# etna-main-driver.net
KiCad netlist of a schematic drawn in Altium Designer
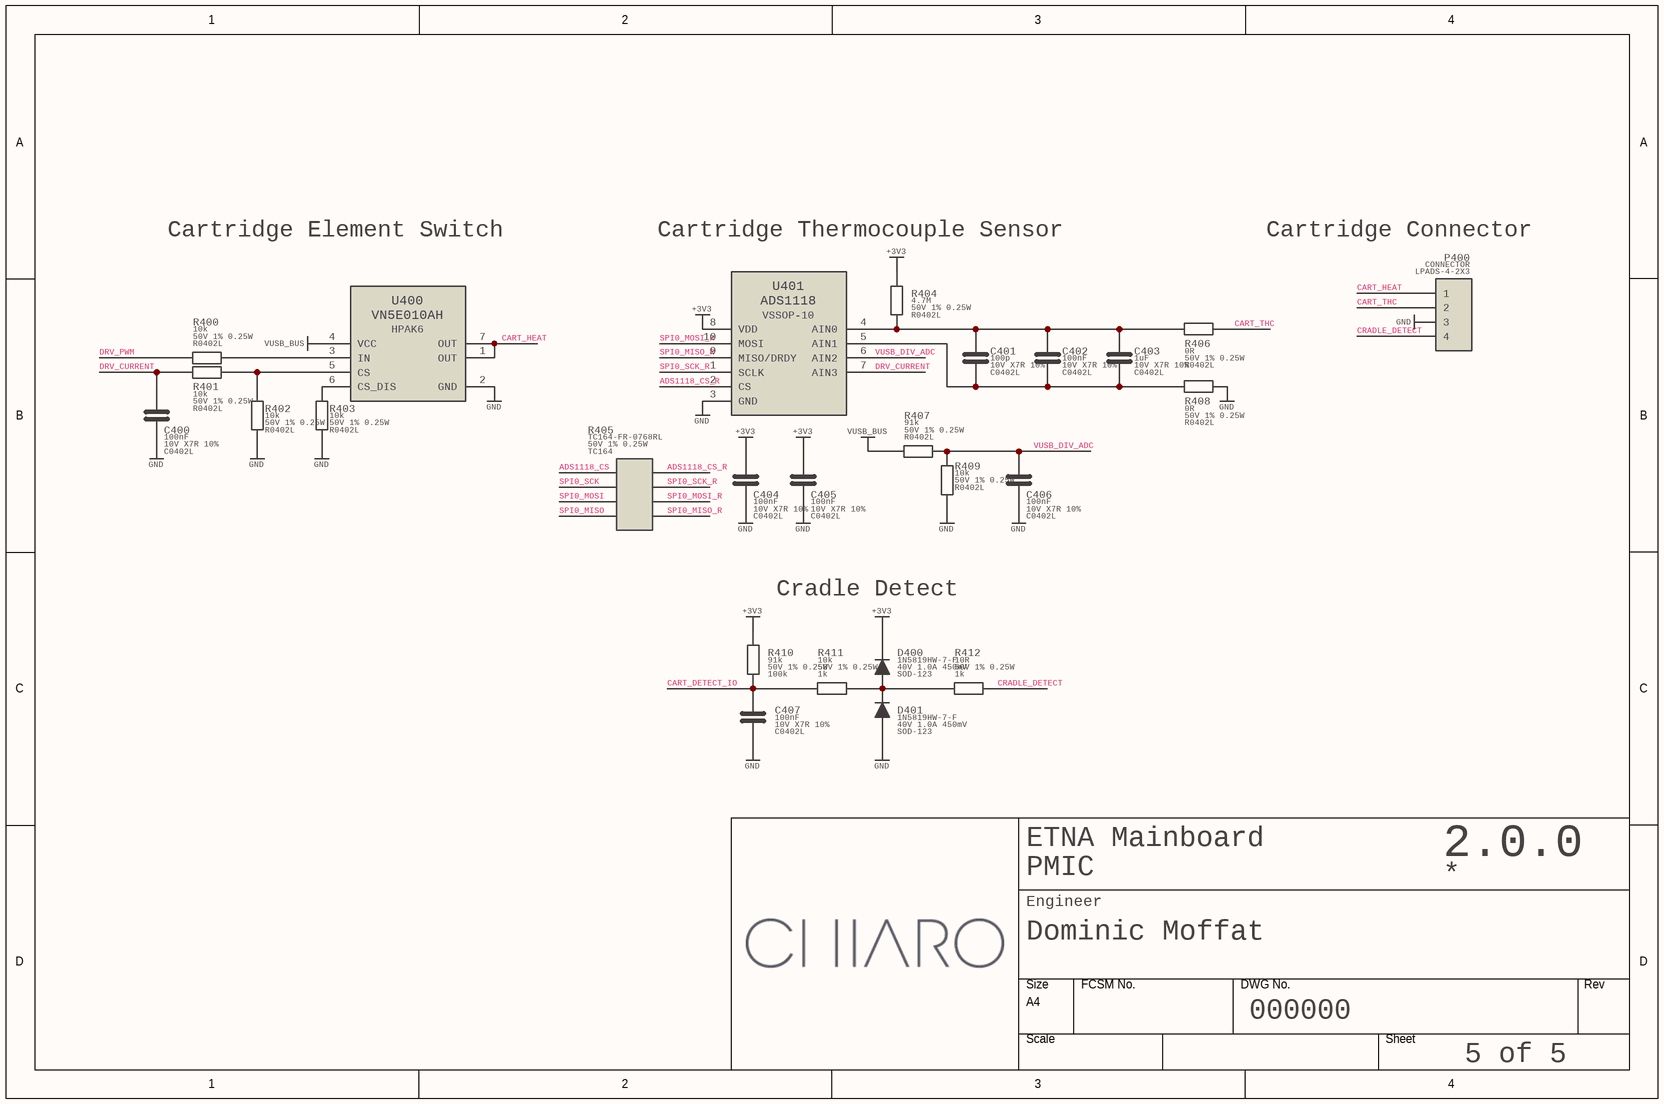
[diagram p0: etna-main-driver.SchDoc]

(export (version "E")
  (design (tool "Eeschema 10.0.6"))
  (components
    (comp (ref "C400")
      (value "100nF")
      (footprint "C0402L")
      (fields (field (name "SPECIFICATION") "10V X7R 10%"))
      (libsource (lib "passive") (part "CAPACITOR_NONPOL"))
    )
    (comp (ref "C401")
      (value "100p")
      (footprint "C0402L")
      (fields (field (name "SPECIFICATION") "10V X7R 10%"))
      (libsource (lib "passive") (part "CAPACITOR_NONPOL"))
    )
    (comp (ref "C402")
      (value "100nF")
      (footprint "C0402L")
      (fields (field (name "SPECIFICATION") "10V X7R 10%"))
      (libsource (lib "passive") (part "CAPACITOR_NONPOL"))
    )
    (comp (ref "C403")
      (value "1uF")
      (footprint "C0402L")
      (fields (field (name "SPECIFICATION") "10V X7R 10%"))
      (libsource (lib "passive") (part "CAPACITOR_NONPOL"))
    )
    (comp (ref "C404")
      (value "100nF")
      (footprint "C0402L")
      (fields (field (name "SPECIFICATION") "10V X7R 10%"))
      (libsource (lib "passive") (part "CAPACITOR_NONPOL"))
    )
    (comp (ref "C405")
      (value "100nF")
      (footprint "C0402L")
      (fields (field (name "SPECIFICATION") "10V X7R 10%"))
      (libsource (lib "passive") (part "CAPACITOR_NONPOL"))
    )
    (comp (ref "C406")
      (value "100nF")
      (footprint "C0402L")
      (fields (field (name "SPECIFICATION") "10V X7R 10%"))
      (libsource (lib "passive") (part "CAPACITOR_NONPOL"))
    )
    (comp (ref "C407")
      (value "100nF")
      (footprint "C0402L")
      (fields (field (name "SPECIFICATION") "10V X7R 10%"))
      (libsource (lib "passive") (part "CAPACITOR_NONPOL"))
    )
    (comp (ref "D400")
      (value "1N5819HW-7-F")
      (footprint "SOD-123")
      (fields (field (name "SPECIFICATION") "40V 1.0A 450mV") (field (name "Comment") "DIODE"))
      (libsource (lib "discreet") (part "DIODE"))
    )
    (comp (ref "D401")
      (value "1N5819HW-7-F")
      (footprint "SOD-123")
      (fields (field (name "SPECIFICATION") "40V 1.0A 450mV") (field (name "Comment") "DIODE"))
      (libsource (lib "discreet") (part "DIODE"))
    )
    (comp (ref "P400")
      (value "CONNECTOR")
      (footprint "LPADS-4-2X3")
      (fields (field (name "Comment") "H4"))
      (libsource (lib "connectors") (part "H4"))
    )
    (comp (ref "R400")
      (value "10k")
      (footprint "R0402L")
      (fields (field (name "SPECIFICATION") "50V 1% 0.25W") (field (name "Comment") "RESISTOR"))
      (libsource (lib "") (part "RESISTOR_1"))
    )
    (comp (ref "R401")
      (value "10k")
      (footprint "R0402L")
      (fields (field (name "SPECIFICATION") "50V 1% 0.25W") (field (name "Comment") "RESISTOR"))
      (libsource (lib "") (part "RESISTOR_1"))
    )
    (comp (ref "R402")
      (value "10k")
      (footprint "R0402L")
      (fields (field (name "SPECIFICATION") "50V 1% 0.25W") (field (name "Comment") "RESISTOR"))
      (libsource (lib "discreet") (part "RESISTOR"))
    )
    (comp (ref "R403")
      (value "10k")
      (footprint "R0402L")
      (fields (field (name "SPECIFICATION") "50V 1% 0.25W") (field (name "Comment") "RESISTOR"))
      (libsource (lib "discreet") (part "RESISTOR"))
    )
    (comp (ref "R404")
      (value "4.7M")
      (footprint "R0402L")
      (fields (field (name "SPECIFICATION") "50V 1% 0.25W") (field (name "Comment") "RESISTOR"))
      (libsource (lib "discreet") (part "RESISTOR"))
    )
    (comp (ref "R405")
      (value "TC164-FR-0768RL")
      (footprint "TC164")
      (fields (field (name "SPECIFICATION") "50V 1% 0.25W") (field (name "Comment") "RESISTOR_4"))
      (libsource (lib "discreet") (part "RESISTOR_4"))
    )
    (comp (ref "R406")
      (value "0R")
      (footprint "R0402L")
      (fields (field (name "SPECIFICATION") "50V 1% 0.25W") (field (name "Comment") "RESISTOR"))
      (libsource (lib "") (part "RESISTOR_1"))
    )
    (comp (ref "R407")
      (value "91k")
      (footprint "R0402L")
      (fields (field (name "SPECIFICATION") "50V 1% 0.25W") (field (name "Comment") "RESISTOR"))
      (libsource (lib "") (part "RESISTOR_3"))
    )
    (comp (ref "R408")
      (value "0R")
      (footprint "R0402L")
      (fields (field (name "SPECIFICATION") "50V 1% 0.25W") (field (name "Comment") "RESISTOR"))
      (libsource (lib "") (part "RESISTOR_1"))
    )
    (comp (ref "R409")
      (value "10k")
      (footprint "R0402L")
      (fields (field (name "SPECIFICATION") "50V 1% 0.25W") (field (name "Comment") "RESISTOR"))
      (libsource (lib "discreet") (part "RESISTOR"))
    )
    (comp (ref "R410")
      (value "91k")
      (footprint "100k")
      (fields (field (name "SPECIFICATION") "50V 1% 0.25W") (field (name "Comment") "RESISTOR"))
      (libsource (lib "") (part "RESISTOR_2"))
    )
    (comp (ref "R411")
      (value "10k")
      (footprint "1k")
      (fields (field (name "SPECIFICATION") "50V 1% 0.25W") (field (name "Comment") "RESISTOR"))
      (libsource (lib "") (part "RESISTOR_1"))
    )
    (comp (ref "R412")
      (value "10R")
      (footprint "1k")
      (fields (field (name "SPECIFICATION") "50V 1% 0.25W") (field (name "Comment") "RESISTOR"))
      (libsource (lib "") (part "RESISTOR_1"))
    )
    (comp (ref "U400") (value "VN5E010AH") (footprint "HPAK6") (libsource (lib "ic") (part "VN5E010AH")))
    (comp (ref "U401") (value "ADS1118") (footprint "VSSOP-10") (libsource (lib "ic") (part "ADS1118")))
  )
  (nets
    (net (code "1") (name "+3V3") (class "Default")
      (node (ref "C404") (pin "1") (pinfunction "1_1") (pintype "passive"))
      (node (ref "C405") (pin "1") (pinfunction "1_1") (pintype "passive"))
      (node (ref "D400") (pin "2") (pinfunction "K_2") (pintype "passive"))
      (node (ref "R404") (pin "2") (pinfunction "2_2") (pintype "passive"))
      (node (ref "R410") (pin "1") (pinfunction "1_1") (pintype "passive"))
      (node (ref "U401") (pin "8") (pinfunction "VDD_8") (pintype "passive"))
    )
    (net (code "2") (name "/ADS1118_CS") (class "Default") (node (ref "R405") (pin "1") (pintype "passive")))
    (net (code "3") (name "/ADS1118_CS_R") (class "Default")
      (node (ref "R405") (pin "8") (pintype "passive"))
      (node (ref "U401") (pin "2") (pinfunction "CS_2") (pintype "passive"))
    )
    (net (code "4") (name "/CART_DETECT_IO") (class "Default")
      (node (ref "C407") (pin "1") (pinfunction "1_1") (pintype "passive"))
      (node (ref "R410") (pin "2") (pinfunction "2_2") (pintype "passive"))
      (node (ref "R411") (pin "2") (pinfunction "2_2") (pintype "passive"))
    )
    (net (code "5") (name "/CART_HEAT") (class "Default")
      (node (ref "P400") (pin "1") (pinfunction "1_1") (pintype "passive"))
      (node (ref "U400") (pin "1") (pinfunction "OUT_1") (pintype "passive"))
      (node (ref "U400") (pin "7") (pinfunction "OUT_7") (pintype "passive"))
    )
    (net (code "6") (name "/CART_THC") (class "Default")
      (node (ref "P400") (pin "2") (pinfunction "2_2") (pintype "passive"))
      (node (ref "R406") (pin "1") (pinfunction "1_1") (pintype "passive"))
    )
    (net (code "7") (name "/CRADLE_DETECT") (class "Default")
      (node (ref "P400") (pin "4") (pinfunction "4_4") (pintype "passive"))
      (node (ref "R412") (pin "1") (pinfunction "1_1") (pintype "passive"))
    )
    (net (code "8") (name "/DRV_CURRENT") (class "Default")
      (node (ref "C400") (pin "1") (pinfunction "1_1") (pintype "passive"))
      (node (ref "R401") (pin "2") (pinfunction "2_2") (pintype "passive"))
      (node (ref "U401") (pin "7") (pinfunction "AIN3_7") (pintype "passive"))
    )
    (net (code "9") (name "/DRV_PWM") (class "Default")
      (node (ref "R400") (pin "2") (pinfunction "2_2") (pintype "passive"))
    )
    (net (code "10") (name "/SPI0_MISO") (class "Default") (node (ref "R405") (pin "4") (pintype "passive")))
    (net (code "11") (name "/SPI0_MISO_R") (class "Default")
      (node (ref "R405") (pin "5") (pintype "passive"))
      (node (ref "U401") (pin "9") (pinfunction "MISO/DRDY_9") (pintype "passive"))
    )
    (net (code "12") (name "/SPI0_MOSI") (class "Default") (node (ref "R405") (pin "3") (pintype "passive")))
    (net (code "13") (name "/SPI0_MOSI_R") (class "Default")
      (node (ref "R405") (pin "6") (pintype "passive"))
      (node (ref "U401") (pin "10") (pinfunction "MOSI_10") (pintype "passive"))
    )
    (net (code "14") (name "/SPI0_SCK") (class "Default") (node (ref "R405") (pin "2") (pintype "passive")))
    (net (code "15") (name "/SPI0_SCK_R") (class "Default")
      (node (ref "R405") (pin "7") (pintype "passive"))
      (node (ref "U401") (pin "1") (pinfunction "SCLK_1") (pintype "passive"))
    )
    (net (code "16") (name "/VUSB_DIV_ADC") (class "Default")
      (node (ref "C406") (pin "1") (pinfunction "1_1") (pintype "passive"))
      (node (ref "R407") (pin "2") (pinfunction "2_2") (pintype "passive"))
      (node (ref "R409") (pin "2") (pinfunction "2_2") (pintype "passive"))
      (node (ref "U401") (pin "6") (pinfunction "AIN2_6") (pintype "passive"))
    )
    (net (code "17") (name "GND") (class "Default")
      (node (ref "C400") (pin "2") (pinfunction "2_2") (pintype "passive"))
      (node (ref "C404") (pin "2") (pinfunction "2_2") (pintype "passive"))
      (node (ref "C405") (pin "2") (pinfunction "2_2") (pintype "passive"))
      (node (ref "C406") (pin "2") (pinfunction "2_2") (pintype "passive"))
      (node (ref "C407") (pin "2") (pinfunction "2_2") (pintype "passive"))
      (node (ref "D401") (pin "1") (pinfunction "A_1") (pintype "passive"))
      (node (ref "P400") (pin "3") (pinfunction "3_3") (pintype "passive"))
      (node (ref "R402") (pin "1") (pinfunction "1_1") (pintype "passive"))
      (node (ref "R403") (pin "1") (pinfunction "1_1") (pintype "passive"))
      (node (ref "R408") (pin "1") (pinfunction "1_1") (pintype "passive"))
      (node (ref "R409") (pin "1") (pinfunction "1_1") (pintype "passive"))
      (node (ref "U400") (pin "2") (pinfunction "GND_2") (pintype "passive"))
      (node (ref "U401") (pin "3") (pinfunction "GND_3") (pintype "passive"))
    )
    (net (code "18") (name "Net-(D400-A)") (class "Default")
      (node (ref "D400") (pin "1") (pinfunction "A_1") (pintype "passive"))
      (node (ref "D401") (pin "2") (pinfunction "K_2") (pintype "passive"))
      (node (ref "R411") (pin "1") (pinfunction "1_1") (pintype "passive"))
      (node (ref "R412") (pin "2") (pinfunction "2_2") (pintype "passive"))
    )
    (net (code "19") (name "Net-(U400-CS)") (class "Default")
      (node (ref "R401") (pin "1") (pinfunction "1_1") (pintype "passive"))
      (node (ref "R402") (pin "2") (pinfunction "2_2") (pintype "passive"))
      (node (ref "U400") (pin "5") (pinfunction "CS_5") (pintype "passive"))
    )
    (net (code "20") (name "Net-(U400-CS_DIS)") (class "Default")
      (node (ref "R403") (pin "2") (pinfunction "2_2") (pintype "passive"))
      (node (ref "U400") (pin "6") (pinfunction "CS_DIS_6") (pintype "passive"))
    )
    (net (code "21") (name "Net-(U400-IN)") (class "Default")
      (node (ref "R400") (pin "1") (pinfunction "1_1") (pintype "passive"))
      (node (ref "U400") (pin "3") (pinfunction "IN_3") (pintype "passive"))
    )
    (net (code "22") (name "Net-(U401-AIN0)") (class "Default")
      (node (ref "C401") (pin "1") (pinfunction "1_1") (pintype "passive"))
      (node (ref "C402") (pin "1") (pinfunction "1_1") (pintype "passive"))
      (node (ref "C403") (pin "1") (pinfunction "1_1") (pintype "passive"))
      (node (ref "R404") (pin "1") (pinfunction "1_1") (pintype "passive"))
      (node (ref "R406") (pin "2") (pinfunction "2_2") (pintype "passive"))
      (node (ref "U401") (pin "4") (pinfunction "AIN0_4") (pintype "passive"))
    )
    (net (code "23") (name "Net-(U401-AIN1)") (class "Default")
      (node (ref "C401") (pin "2") (pinfunction "2_2") (pintype "passive"))
      (node (ref "C402") (pin "2") (pinfunction "2_2") (pintype "passive"))
      (node (ref "C403") (pin "2") (pinfunction "2_2") (pintype "passive"))
      (node (ref "R408") (pin "2") (pinfunction "2_2") (pintype "passive"))
      (node (ref "U401") (pin "5") (pinfunction "AIN1_5") (pintype "passive"))
    )
    (net (code "24") (name "VUSB_BUS") (class "Default")
      (node (ref "R407") (pin "1") (pinfunction "1_1") (pintype "passive"))
      (node (ref "U400") (pin "4") (pinfunction "VCC_4") (pintype "passive"))
    )
    (net (code "25") (name "unconnected-(U400-N.C.-Pad44)") (class "Default")
      (node (ref "U400") (pin "44") (pinfunction "N.C._44") (pintype "passive"))
    )
    (net (code "26") (name "unconnected-(U401-N.C.-Pad44)") (class "Default")
      (node (ref "U401") (pin "44") (pinfunction "N.C._44") (pintype "passive"))
    )
  )
)
